# Memory_GPIO.net
KiCad netlist of a schematic drawn in Altium Designer
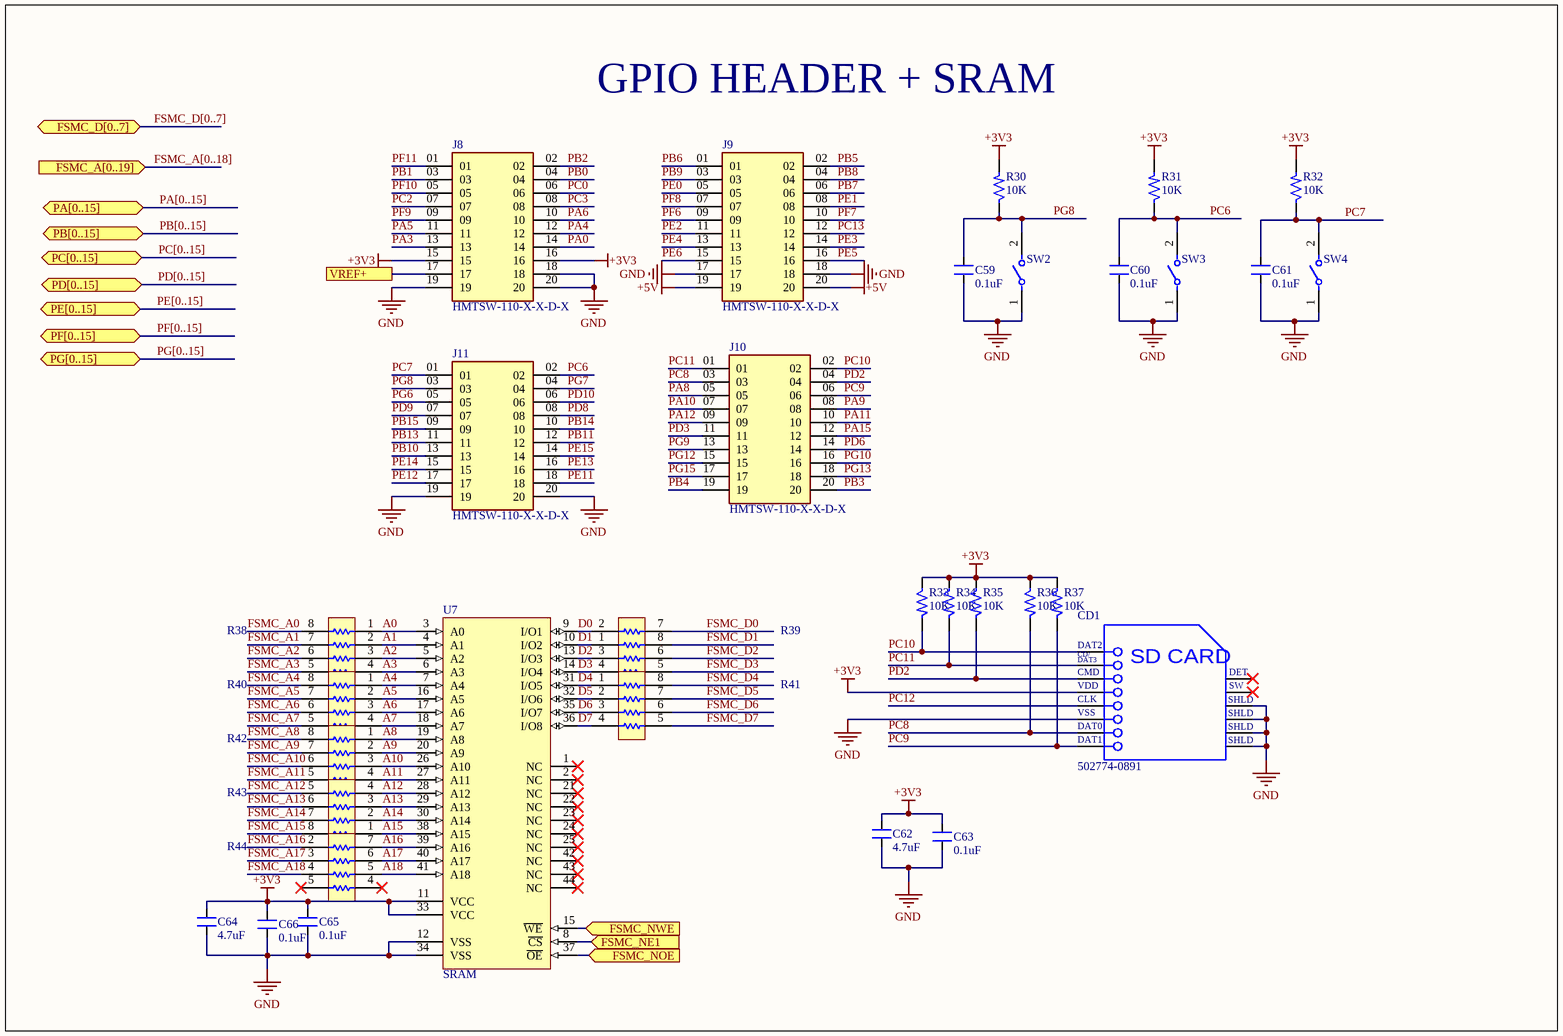
[diagram p0: Memory+GPIO.SchDoc]

(export (version "E")
  (design (tool "Eeschema 10.0.6"))
  (components
    (comp (ref "C59")
      (value "0.1uF")
      (footprint "CAP_0805")
      (description "0.1µF ±10% 50V Ceramic Capacitor X7R 0805 (2012 Metric)")
      (fields
        (field (name "MANUFACTURER") "Samsung")
        (field (name "MANUFACTURER PART NUMBER") "CL21B104KBCNNNC")
      )
      (libsource (lib "ESTEEMPCBLIB") (part "CAP_0.1uF-50V-10%-0805"))
    )
    (comp (ref "C60")
      (value "0.1uF")
      (footprint "CAP_0805")
      (description "0.1µF ±10% 50V Ceramic Capacitor X7R 0805 (2012 Metric)")
      (fields
        (field (name "MANUFACTURER") "Samsung")
        (field (name "MANUFACTURER PART NUMBER") "CL21B104KBCNNNC")
      )
      (libsource (lib "ESTEEMPCBLIB") (part "CAP_0.1uF-50V-10%-0805"))
    )
    (comp (ref "C61")
      (value "0.1uF")
      (footprint "CAP_0805")
      (description "0.1µF ±10% 50V Ceramic Capacitor X7R 0805 (2012 Metric)")
      (fields
        (field (name "MANUFACTURER") "Samsung")
        (field (name "MANUFACTURER PART NUMBER") "CL21B104KBCNNNC")
      )
      (libsource (lib "ESTEEMPCBLIB") (part "CAP_0.1uF-50V-10%-0805"))
    )
    (comp (ref "C62")
      (value "4.7uF")
      (footprint "CAP_0805")
      (description "4.7µF ±10% 50V Ceramic Capacitor X5R 0805 (2012 Metric)")
      (fields
        (field (name "MANUFACTURER") "Yageo")
        (field (name "MANUFACTURER PART NUMBER") "GRM21BR61H475KE51L")
      )
      (libsource (lib "ESTEEMPCBLIB") (part "CAP_4.7uF-50V-10%-0805"))
    )
    (comp (ref "C63")
      (value "0.1uF")
      (footprint "CAP_0805")
      (description "0.1µF ±10% 50V Ceramic Capacitor X7R 0805 (2012 Metric)")
      (fields
        (field (name "MANUFACTURER") "Samsung")
        (field (name "MANUFACTURER PART NUMBER") "CL21B104KBCNNNC")
      )
      (libsource (lib "ESTEEMPCBLIB") (part "CAP_0.1uF-50V-10%-0805"))
    )
    (comp (ref "C64")
      (value "4.7uF")
      (footprint "CAP_0805")
      (description "4.7µF ±10% 50V Ceramic Capacitor X5R 0805 (2012 Metric)")
      (fields
        (field (name "MANUFACTURER") "Yageo")
        (field (name "MANUFACTURER PART NUMBER") "GRM21BR61H475KE51L")
      )
      (libsource (lib "ESTEEMPCBLIB") (part "CAP_4.7uF-50V-10%-0805"))
    )
    (comp (ref "C65")
      (value "0.1uF")
      (footprint "CAP_0805")
      (description "0.1µF ±10% 50V Ceramic Capacitor X7R 0805 (2012 Metric)")
      (fields
        (field (name "MANUFACTURER") "Samsung")
        (field (name "MANUFACTURER PART NUMBER") "CL21B104KBCNNNC")
      )
      (libsource (lib "ESTEEMPCBLIB") (part "CAP_0.1uF-50V-10%-0805"))
    )
    (comp (ref "C66")
      (value "0.1uF")
      (footprint "CAP_0805")
      (description "0.1µF ±10% 50V Ceramic Capacitor X7R 0805 (2012 Metric)")
      (fields
        (field (name "MANUFACTURER") "Samsung")
        (field (name "MANUFACTURER PART NUMBER") "CL21B104KBCNNNC")
      )
      (libsource (lib "ESTEEMPCBLIB") (part "CAP_0.1uF-50V-10%-0805"))
    )
    (comp (ref "CD1")
      (value "502774-0891")
      (footprint "MOLX-502774-0891_V")
      (description "Micro SD Memory Card Connector, 0.5 A, 10 V (DC), -25 to 85 degC, 8-Pin SMT, RoHS, Tape and Reel")
      (fields (field (name "MANUFACTURER") "Molex"))
      (libsource (lib "Altium Content Vault") (part "CN-SD-8-2SW-4S_B"))
    )
    (comp (ref "J8")
      (value "HMTSW-110-X-X-D-X")
      (footprint "SAMTEC_HMTSW-110-X-X-D-X")
      (fields (field (name "MF") "Samtec") (field (name "MP") "HMTSW11008LMD330"))
      (libsource (lib "ESTEEMPCBLIB") (part "HMTSW-110-X-X-D-X"))
    )
    (comp (ref "J9")
      (value "HMTSW-110-X-X-D-X")
      (footprint "SAMTEC_HMTSW-110-X-X-D-X")
      (fields (field (name "MF") "Samtec") (field (name "MP") "HMTSW11008LMD330"))
      (libsource (lib "ESTEEMPCBLIB") (part "HMTSW-110-X-X-D-X"))
    )
    (comp (ref "J10")
      (value "HMTSW-110-X-X-D-X")
      (footprint "SAMTEC_HMTSW-110-X-X-D-X")
      (fields (field (name "MF") "Samtec") (field (name "MP") "HMTSW11008LMD330"))
      (libsource (lib "ESTEEMPCBLIB") (part "HMTSW-110-X-X-D-X"))
    )
    (comp (ref "J11")
      (value "HMTSW-110-X-X-D-X")
      (footprint "SAMTEC_HMTSW-110-X-X-D-X")
      (fields (field (name "MF") "Samtec") (field (name "MP") "HMTSW11008LMD330"))
      (libsource (lib "ESTEEMPCBLIB") (part "HMTSW-110-X-X-D-X"))
    )
    (comp (ref "R30")
      (value "10K")
      (footprint "RES_0603")
      (description "10 kOhms ±1% 0.1W, 1/10W Chip Resistor 0603 (1608 Metric) Automotive AEC-Q200 Thick Film")
      (fields (field (name "MANUFACTURER") "Walsin") (field (name "MANUFACTURER PART NUMBER") "WR06X1002FTL"))
      (libsource (lib "ESTEEMPCBLIB") (part "RES_10K-0.1W-1%-0603"))
    )
    (comp (ref "R31")
      (value "10K")
      (footprint "RES_0603")
      (description "10 kOhms ±1% 0.1W, 1/10W Chip Resistor 0603 (1608 Metric) Automotive AEC-Q200 Thick Film")
      (fields (field (name "MANUFACTURER") "Walsin") (field (name "MANUFACTURER PART NUMBER") "WR06X1002FTL"))
      (libsource (lib "ESTEEMPCBLIB") (part "RES_10K-0.1W-1%-0603"))
    )
    (comp (ref "R32")
      (value "10K")
      (footprint "RES_0603")
      (description "10 kOhms ±1% 0.1W, 1/10W Chip Resistor 0603 (1608 Metric) Automotive AEC-Q200 Thick Film")
      (fields (field (name "MANUFACTURER") "Walsin") (field (name "MANUFACTURER PART NUMBER") "WR06X1002FTL"))
      (libsource (lib "ESTEEMPCBLIB") (part "RES_10K-0.1W-1%-0603"))
    )
    (comp (ref "R33")
      (value "10K")
      (footprint "RES_0805")
      (description "10 kOhms ±1% 0.125W, 1/8W Chip Resistor 0805 (2012 Metric) Automotive AEC-Q200 Thick Film")
      (fields (field (name "MANUFACTURER") "CTS") (field (name "MANUFACTURER PART NUMBER") "WR08X1002FTL"))
      (libsource (lib "ESTEEMPCBLIB") (part "RES_10K-0.125W-1%-0805"))
    )
    (comp (ref "R34")
      (value "10K")
      (footprint "RES_0805")
      (description "10 kOhms ±1% 0.125W, 1/8W Chip Resistor 0805 (2012 Metric) Automotive AEC-Q200 Thick Film")
      (fields (field (name "MANUFACTURER") "CTS") (field (name "MANUFACTURER PART NUMBER") "WR08X1002FTL"))
      (libsource (lib "ESTEEMPCBLIB") (part "RES_10K-0.125W-1%-0805"))
    )
    (comp (ref "R35")
      (value "10K")
      (footprint "RES_0805")
      (description "10 kOhms ±1% 0.125W, 1/8W Chip Resistor 0805 (2012 Metric) Automotive AEC-Q200 Thick Film")
      (fields (field (name "MANUFACTURER") "CTS") (field (name "MANUFACTURER PART NUMBER") "WR08X1002FTL"))
      (libsource (lib "ESTEEMPCBLIB") (part "RES_10K-0.125W-1%-0805"))
    )
    (comp (ref "R36")
      (value "10K")
      (footprint "RES_0805")
      (description "10 kOhms ±1% 0.125W, 1/8W Chip Resistor 0805 (2012 Metric) Automotive AEC-Q200 Thick Film")
      (fields (field (name "MANUFACTURER") "CTS") (field (name "MANUFACTURER PART NUMBER") "WR08X1002FTL"))
      (libsource (lib "ESTEEMPCBLIB") (part "RES_10K-0.125W-1%-0805"))
    )
    (comp (ref "R37")
      (value "10K")
      (footprint "RES_0805")
      (description "10 kOhms ±1% 0.125W, 1/8W Chip Resistor 0805 (2012 Metric) Automotive AEC-Q200 Thick Film")
      (fields (field (name "MANUFACTURER") "CTS") (field (name "MANUFACTURER PART NUMBER") "WR08X1002FTL"))
      (libsource (lib "ESTEEMPCBLIB") (part "RES_10K-0.125W-1%-0805"))
    )
    (comp (ref "R38")
      (value "CAT16-103J4LF")
      (footprint "BOUR-CAT16-103J4LF_L")
      (fields (field (name "MANUFACTURER") "Bourns") (field (name "TOLERANCE") "±5%"))
      (libsource (lib "Altium Content Vault") (part "RES-P-8"))
    )
    (comp (ref "R39")
      (value "CAT16-103J4LF")
      (footprint "BOUR-CAT16-103J4LF_L")
      (fields (field (name "MANUFACTURER") "Bourns") (field (name "TOLERANCE") "±5%"))
      (libsource (lib "") (part "RES-P-8_3"))
    )
    (comp (ref "R40")
      (value "CAT16-103J4LF")
      (footprint "BOUR-CAT16-103J4LF_L")
      (fields (field (name "MANUFACTURER") "Bourns") (field (name "TOLERANCE") "±5%"))
      (libsource (lib "Altium Content Vault") (part "RES-P-8"))
    )
    (comp (ref "R41")
      (value "CAT16-103J4LF")
      (footprint "BOUR-CAT16-103J4LF_L")
      (fields (field (name "MANUFACTURER") "Bourns") (field (name "TOLERANCE") "±5%"))
      (libsource (lib "") (part "RES-P-8_2"))
    )
    (comp (ref "R42")
      (value "CAT16-103J4LF")
      (footprint "BOUR-CAT16-103J4LF_L")
      (fields (field (name "MANUFACTURER") "Bourns") (field (name "TOLERANCE") "±5%"))
      (libsource (lib "Altium Content Vault") (part "RES-P-8"))
    )
    (comp (ref "R43")
      (value "CAT16-103J4LF")
      (footprint "BOUR-CAT16-103J4LF_L")
      (fields (field (name "MANUFACTURER") "Bourns") (field (name "TOLERANCE") "±5%"))
      (libsource (lib "") (part "RES-P-8_1"))
    )
    (comp (ref "R44")
      (value "CAT16-103J4LF")
      (footprint "BOUR-CAT16-103J4LF_L")
      (fields (field (name "MANUFACTURER") "Bourns") (field (name "TOLERANCE") "±5%"))
      (libsource (lib "") (part "RES-P-8_4"))
    )
    (comp (ref "SW2")
      (value "147873-1")
      (footprint "FP-147873-1-MFG")
      (description "SWITCH TACTILE SPST-NO 0.05A 24V")
      (fields
        (field (name "MANUFACTURER") "TE Connectivity")
        (field (name "OCTOPART") "https://octopart.com/147873-1-te+connectivity-40818451")
      )
      (libsource (lib "Altium Content Vault") (part "bb27bde45df87f1f469753f287ef5ae"))
    )
    (comp (ref "SW3")
      (value "147873-1")
      (footprint "FP-147873-1-MFG")
      (description "SWITCH TACTILE SPST-NO 0.05A 24V")
      (fields
        (field (name "MANUFACTURER") "TE Connectivity")
        (field (name "OCTOPART") "https://octopart.com/147873-1-te+connectivity-40818451")
      )
      (libsource (lib "Altium Content Vault") (part "bb27bde45df87f1f469753f287ef5ae"))
    )
    (comp (ref "SW4")
      (value "147873-1")
      (footprint "FP-147873-1-MFG")
      (description "SWITCH TACTILE SPST-NO 0.05A 24V")
      (fields
        (field (name "MANUFACTURER") "TE Connectivity")
        (field (name "OCTOPART") "https://octopart.com/147873-1-te+connectivity-40818451")
      )
      (libsource (lib "Altium Content Vault") (part "bb27bde45df87f1f469753f287ef5ae"))
    )
    (comp (ref "U7")
      (value "SRAM")
      (footprint "CYP-TSOP-44_L")
      (description "4-Mbit (256 K x 16) Static RAM, 3 to 3.6 V, -40 to 85 degC, 44-Pin TSOP, RoHS, Tray")
      (fields (field (name "MANUFACTURER") "Cypress"))
      (libsource (lib "Persional LIB") (part "CMP-2000-06133-1"))
    )
  )
  (nets
    (net (code "44") (name "+3V3") (class "Default")
      (node (ref "C62") (pin "2") (pinfunction "2_2") (pintype "passive"))
      (node (ref "C63") (pin "2") (pinfunction "2_2") (pintype "passive"))
      (node (ref "C64") (pin "2") (pinfunction "2_2") (pintype "passive"))
      (node (ref "C65") (pin "2") (pinfunction "2_2") (pintype "passive"))
      (node (ref "C66") (pin "2") (pinfunction "2_2") (pintype "passive"))
      (node (ref "CD1") (pin "4") (pinfunction "VDD_4") (pintype "passive"))
      (node (ref "J8") (pin "15") (pinfunction "15_15") (pintype "passive"))
      (node (ref "J8") (pin "16") (pinfunction "16_16") (pintype "passive"))
      (node (ref "R30") (pin "2") (pinfunction "2_2") (pintype "passive"))
      (node (ref "R31") (pin "2") (pinfunction "2_2") (pintype "passive"))
      (node (ref "R32") (pin "2") (pinfunction "2_2") (pintype "passive"))
      (node (ref "R33") (pin "1") (pinfunction "1_1") (pintype "passive"))
      (node (ref "R34") (pin "1") (pinfunction "1_1") (pintype "passive"))
      (node (ref "R35") (pin "1") (pinfunction "1_1") (pintype "passive"))
      (node (ref "R36") (pin "1") (pinfunction "1_1") (pintype "passive"))
      (node (ref "R37") (pin "1") (pinfunction "1_1") (pintype "passive"))
      (node (ref "U7") (pin "11") (pinfunction "VCC_11") (pintype "power_in"))
      (node (ref "U7") (pin "33") (pinfunction "VCC_33") (pintype "power_in"))
    )
    (net (code "45") (name "+5V") (class "Default")
      (node (ref "J9") (pin "19") (pinfunction "19_19") (pintype "passive"))
      (node (ref "J9") (pin "20") (pinfunction "20_20") (pintype "passive"))
    )
    (net (code "46") (name "/A0") (class "Default")
      (node (ref "R38") (pin "1") (pinfunction "4_1") (pintype "passive"))
      (node (ref "U7") (pin "3") (pinfunction "A0_3") (pintype "input"))
    )
    (net (code "47") (name "/A1") (class "Default")
      (node (ref "R38") (pin "2") (pinfunction "3_2") (pintype "passive"))
      (node (ref "U7") (pin "4") (pinfunction "A1_4") (pintype "input"))
    )
    (net (code "48") (name "/A2") (class "Default")
      (node (ref "R38") (pin "3") (pinfunction "2_3") (pintype "passive"))
      (node (ref "U7") (pin "5") (pinfunction "A2_5") (pintype "input"))
    )
    (net (code "49") (name "/A3") (class "Default")
      (node (ref "R38") (pin "4") (pinfunction "1_4") (pintype "passive"))
      (node (ref "U7") (pin "6") (pinfunction "A3_6") (pintype "input"))
    )
    (net (code "50") (name "/A4") (class "Default")
      (node (ref "R40") (pin "1") (pinfunction "4_1") (pintype "passive"))
      (node (ref "U7") (pin "7") (pinfunction "A4_7") (pintype "input"))
    )
    (net (code "51") (name "/A5") (class "Default")
      (node (ref "R40") (pin "2") (pinfunction "3_2") (pintype "passive"))
      (node (ref "U7") (pin "16") (pinfunction "A5_16") (pintype "input"))
    )
    (net (code "52") (name "/A6") (class "Default")
      (node (ref "R40") (pin "3") (pinfunction "2_3") (pintype "passive"))
      (node (ref "U7") (pin "17") (pinfunction "A6_17") (pintype "input"))
    )
    (net (code "53") (name "/A7") (class "Default")
      (node (ref "R40") (pin "4") (pinfunction "1_4") (pintype "passive"))
      (node (ref "U7") (pin "18") (pinfunction "A7_18") (pintype "input"))
    )
    (net (code "54") (name "/A8") (class "Default")
      (node (ref "R42") (pin "1") (pinfunction "4_1") (pintype "passive"))
      (node (ref "U7") (pin "19") (pinfunction "A8_19") (pintype "input"))
    )
    (net (code "55") (name "/A9") (class "Default")
      (node (ref "R42") (pin "2") (pinfunction "3_2") (pintype "passive"))
      (node (ref "U7") (pin "20") (pinfunction "A9_20") (pintype "input"))
    )
    (net (code "56") (name "/A10") (class "Default")
      (node (ref "R42") (pin "3") (pinfunction "2_3") (pintype "passive"))
      (node (ref "U7") (pin "26") (pinfunction "A10_26") (pintype "input"))
    )
    (net (code "57") (name "/A11") (class "Default")
      (node (ref "R42") (pin "4") (pinfunction "1_4") (pintype "passive"))
      (node (ref "U7") (pin "27") (pinfunction "A11_27") (pintype "input"))
    )
    (net (code "58") (name "/A12") (class "Default")
      (node (ref "R43") (pin "4") (pinfunction "4_4") (pintype "passive"))
      (node (ref "U7") (pin "28") (pinfunction "A12_28") (pintype "input"))
    )
    (net (code "59") (name "/A13") (class "Default")
      (node (ref "R43") (pin "3") (pinfunction "3_3") (pintype "passive"))
      (node (ref "U7") (pin "29") (pinfunction "A13_29") (pintype "input"))
    )
    (net (code "60") (name "/A14") (class "Default")
      (node (ref "R43") (pin "2") (pinfunction "2_2") (pintype "passive"))
      (node (ref "U7") (pin "30") (pinfunction "A14_30") (pintype "input"))
    )
    (net (code "61") (name "/A15") (class "Default")
      (node (ref "R43") (pin "1") (pinfunction "1_1") (pintype "passive"))
      (node (ref "U7") (pin "38") (pinfunction "A15_38") (pintype "input"))
    )
    (net (code "62") (name "/A16") (class "Default")
      (node (ref "R44") (pin "7") (pinfunction "4_7") (pintype "passive"))
      (node (ref "U7") (pin "39") (pinfunction "A16_39") (pintype "input"))
    )
    (net (code "63") (name "/A17") (class "Default")
      (node (ref "R44") (pin "6") (pinfunction "3_6") (pintype "passive"))
      (node (ref "U7") (pin "40") (pinfunction "A17_40") (pintype "input"))
    )
    (net (code "64") (name "/A18") (class "Default")
      (node (ref "R44") (pin "5") (pinfunction "2_5") (pintype "passive"))
      (node (ref "U7") (pin "41") (pinfunction "A18_41") (pintype "input"))
    )
    (net (code "65") (name "/D0") (class "Default")
      (node (ref "R39") (pin "2") (pinfunction "1_2") (pintype "passive"))
      (node (ref "U7") (pin "9") (pinfunction "I/O1_9") (pintype "bidirectional"))
    )
    (net (code "66") (name "/D1") (class "Default")
      (node (ref "R39") (pin "1") (pinfunction "2_1") (pintype "passive"))
      (node (ref "U7") (pin "10") (pinfunction "I/O2_10") (pintype "bidirectional"))
    )
    (net (code "67") (name "/D2") (class "Default")
      (node (ref "R39") (pin "3") (pinfunction "3_3") (pintype "passive"))
      (node (ref "U7") (pin "13") (pinfunction "I/O3_13") (pintype "bidirectional"))
    )
    (net (code "68") (name "/D3") (class "Default")
      (node (ref "R39") (pin "4") (pinfunction "4_4") (pintype "passive"))
      (node (ref "U7") (pin "14") (pinfunction "I/O4_14") (pintype "bidirectional"))
    )
    (net (code "69") (name "/D4") (class "Default")
      (node (ref "R41") (pin "1") (pinfunction "1_1") (pintype "passive"))
      (node (ref "U7") (pin "31") (pinfunction "I/O5_31") (pintype "bidirectional"))
    )
    (net (code "70") (name "/D5") (class "Default")
      (node (ref "R41") (pin "2") (pinfunction "2_2") (pintype "passive"))
      (node (ref "U7") (pin "32") (pinfunction "I/O6_32") (pintype "bidirectional"))
    )
    (net (code "71") (name "/D6") (class "Default")
      (node (ref "R41") (pin "3") (pinfunction "3_3") (pintype "passive"))
      (node (ref "U7") (pin "35") (pinfunction "I/O7_35") (pintype "bidirectional"))
    )
    (net (code "72") (name "/D7") (class "Default")
      (node (ref "R41") (pin "4") (pinfunction "4_4") (pintype "passive"))
      (node (ref "U7") (pin "36") (pinfunction "I/O8_36") (pintype "bidirectional"))
    )
    (net (code "73") (name "/FSMC_A0") (class "Default")
      (node (ref "R38") (pin "8") (pinfunction "5_8") (pintype "passive"))
    )
    (net (code "74") (name "/FSMC_A1") (class "Default")
      (node (ref "R38") (pin "7") (pinfunction "6_7") (pintype "passive"))
    )
    (net (code "75") (name "/FSMC_A2") (class "Default")
      (node (ref "R38") (pin "6") (pinfunction "7_6") (pintype "passive"))
    )
    (net (code "76") (name "/FSMC_A3") (class "Default")
      (node (ref "R38") (pin "5") (pinfunction "8_5") (pintype "passive"))
    )
    (net (code "77") (name "/FSMC_A4") (class "Default")
      (node (ref "R40") (pin "8") (pinfunction "5_8") (pintype "passive"))
    )
    (net (code "78") (name "/FSMC_A5") (class "Default")
      (node (ref "R40") (pin "7") (pinfunction "6_7") (pintype "passive"))
    )
    (net (code "79") (name "/FSMC_A6") (class "Default")
      (node (ref "R40") (pin "6") (pinfunction "7_6") (pintype "passive"))
    )
    (net (code "80") (name "/FSMC_A7") (class "Default")
      (node (ref "R40") (pin "5") (pinfunction "8_5") (pintype "passive"))
    )
    (net (code "81") (name "/FSMC_A8") (class "Default")
      (node (ref "R42") (pin "8") (pinfunction "5_8") (pintype "passive"))
    )
    (net (code "82") (name "/FSMC_A9") (class "Default")
      (node (ref "R42") (pin "7") (pinfunction "6_7") (pintype "passive"))
    )
    (net (code "83") (name "/FSMC_A10") (class "Default")
      (node (ref "R42") (pin "6") (pinfunction "7_6") (pintype "passive"))
    )
    (net (code "84") (name "/FSMC_A11") (class "Default")
      (node (ref "R42") (pin "5") (pinfunction "8_5") (pintype "passive"))
    )
    (net (code "85") (name "/FSMC_A12") (class "Default")
      (node (ref "R43") (pin "5") (pinfunction "5_5") (pintype "passive"))
    )
    (net (code "86") (name "/FSMC_A13") (class "Default")
      (node (ref "R43") (pin "6") (pinfunction "6_6") (pintype "passive"))
    )
    (net (code "87") (name "/FSMC_A14") (class "Default")
      (node (ref "R43") (pin "7") (pinfunction "7_7") (pintype "passive"))
    )
    (net (code "88") (name "/FSMC_A15") (class "Default")
      (node (ref "R43") (pin "8") (pinfunction "8_8") (pintype "passive"))
    )
    (net (code "89") (name "/FSMC_A16") (class "Default")
      (node (ref "R44") (pin "2") (pinfunction "5_2") (pintype "passive"))
    )
    (net (code "90") (name "/FSMC_A17") (class "Default")
      (node (ref "R44") (pin "3") (pinfunction "6_3") (pintype "passive"))
    )
    (net (code "91") (name "/FSMC_A18") (class "Default")
      (node (ref "R44") (pin "4") (pinfunction "7_4") (pintype "passive"))
    )
    (net (code "93") (name "/FSMC_D0") (class "Default")
      (node (ref "R39") (pin "7") (pinfunction "8_7") (pintype "passive"))
    )
    (net (code "94") (name "/FSMC_D1") (class "Default")
      (node (ref "R39") (pin "8") (pinfunction "7_8") (pintype "passive"))
    )
    (net (code "95") (name "/FSMC_D2") (class "Default")
      (node (ref "R39") (pin "6") (pinfunction "6_6") (pintype "passive"))
    )
    (net (code "96") (name "/FSMC_D3") (class "Default")
      (node (ref "R39") (pin "5") (pinfunction "5_5") (pintype "passive"))
    )
    (net (code "97") (name "/FSMC_D4") (class "Default")
      (node (ref "R41") (pin "8") (pinfunction "8_8") (pintype "passive"))
    )
    (net (code "98") (name "/FSMC_D5") (class "Default")
      (node (ref "R41") (pin "7") (pinfunction "7_7") (pintype "passive"))
    )
    (net (code "99") (name "/FSMC_D6") (class "Default")
      (node (ref "R41") (pin "6") (pinfunction "6_6") (pintype "passive"))
    )
    (net (code "100") (name "/FSMC_D7") (class "Default")
      (node (ref "R41") (pin "5") (pinfunction "5_5") (pintype "passive"))
    )
    (net (code "102") (name "/FSMC_NE1") (class "Default")
      (node (ref "U7") (pin "8") (pinfunction "~{CS}_8") (pintype "input"))
    )
    (net (code "103") (name "/FSMC_NOE") (class "Default")
      (node (ref "U7") (pin "37") (pinfunction "~{OE}_37") (pintype "input"))
    )
    (net (code "104") (name "/FSMC_NWE") (class "Default")
      (node (ref "U7") (pin "15") (pinfunction "~{WE}_15") (pintype "input"))
    )
    (net (code "105") (name "/PA0") (class "Default")
      (node (ref "J8") (pin "14") (pinfunction "14_14") (pintype "passive"))
    )
    (net (code "106") (name "/PA3") (class "Default")
      (node (ref "J8") (pin "13") (pinfunction "13_13") (pintype "passive"))
    )
    (net (code "107") (name "/PA4") (class "Default")
      (node (ref "J8") (pin "12") (pinfunction "12_12") (pintype "passive"))
    )
    (net (code "108") (name "/PA5") (class "Default")
      (node (ref "J8") (pin "11") (pinfunction "11_11") (pintype "passive"))
    )
    (net (code "109") (name "/PA6") (class "Default")
      (node (ref "J8") (pin "10") (pinfunction "10_10") (pintype "passive"))
    )
    (net (code "110") (name "/PA8") (class "Default")
      (node (ref "J10") (pin "05") (pinfunction "05_05") (pintype "passive"))
    )
    (net (code "111") (name "/PA9") (class "Default")
      (node (ref "J10") (pin "08") (pinfunction "08_08") (pintype "passive"))
    )
    (net (code "112") (name "/PA10") (class "Default")
      (node (ref "J10") (pin "07") (pinfunction "07_07") (pintype "passive"))
    )
    (net (code "113") (name "/PA11") (class "Default")
      (node (ref "J10") (pin "10") (pinfunction "10_10") (pintype "passive"))
    )
    (net (code "114") (name "/PA12") (class "Default")
      (node (ref "J10") (pin "09") (pinfunction "09_09") (pintype "passive"))
    )
    (net (code "115") (name "/PA15") (class "Default")
      (node (ref "J10") (pin "12") (pinfunction "12_12") (pintype "passive"))
    )
    (net (code "117") (name "/PB0") (class "Default")
      (node (ref "J8") (pin "04") (pinfunction "04_04") (pintype "passive"))
    )
    (net (code "118") (name "/PB1") (class "Default")
      (node (ref "J8") (pin "03") (pinfunction "03_03") (pintype "passive"))
    )
    (net (code "119") (name "/PB2") (class "Default")
      (node (ref "J8") (pin "02") (pinfunction "02_02") (pintype "passive"))
    )
    (net (code "120") (name "/PB3") (class "Default")
      (node (ref "J10") (pin "20") (pinfunction "20_20") (pintype "passive"))
    )
    (net (code "121") (name "/PB4") (class "Default")
      (node (ref "J10") (pin "19") (pinfunction "19_19") (pintype "passive"))
    )
    (net (code "122") (name "/PB5") (class "Default")
      (node (ref "J9") (pin "02") (pinfunction "02_02") (pintype "passive"))
    )
    (net (code "123") (name "/PB6") (class "Default")
      (node (ref "J9") (pin "01") (pinfunction "01_01") (pintype "passive"))
    )
    (net (code "124") (name "/PB7") (class "Default")
      (node (ref "J9") (pin "06") (pinfunction "06_06") (pintype "passive"))
    )
    (net (code "125") (name "/PB8") (class "Default")
      (node (ref "J9") (pin "04") (pinfunction "04_04") (pintype "passive"))
    )
    (net (code "126") (name "/PB9") (class "Default")
      (node (ref "J9") (pin "03") (pinfunction "03_03") (pintype "passive"))
    )
    (net (code "127") (name "/PB10") (class "Default")
      (node (ref "J11") (pin "13") (pinfunction "13_13") (pintype "passive"))
    )
    (net (code "128") (name "/PB11") (class "Default")
      (node (ref "J11") (pin "12") (pinfunction "12_12") (pintype "passive"))
    )
    (net (code "129") (name "/PB13") (class "Default")
      (node (ref "J11") (pin "11") (pinfunction "11_11") (pintype "passive"))
    )
    (net (code "130") (name "/PB14") (class "Default")
      (node (ref "J11") (pin "10") (pinfunction "10_10") (pintype "passive"))
    )
    (net (code "131") (name "/PB15") (class "Default")
      (node (ref "J11") (pin "09") (pinfunction "09_09") (pintype "passive"))
    )
    (net (code "133") (name "/PC0") (class "Default")
      (node (ref "J8") (pin "06") (pinfunction "06_06") (pintype "passive"))
    )
    (net (code "134") (name "/PC2") (class "Default")
      (node (ref "J8") (pin "07") (pinfunction "07_07") (pintype "passive"))
    )
    (net (code "135") (name "/PC3") (class "Default")
      (node (ref "J8") (pin "08") (pinfunction "08_08") (pintype "passive"))
    )
    (net (code "136") (name "/PC6") (class "Default")
      (node (ref "C60") (pin "2") (pinfunction "2_2") (pintype "passive"))
      (node (ref "J11") (pin "02") (pinfunction "02_02") (pintype "passive"))
      (node (ref "R31") (pin "1") (pinfunction "1_1") (pintype "passive"))
      (node (ref "SW3") (pin "2") (pinfunction "2_2") (pintype "passive"))
    )
    (net (code "137") (name "/PC7") (class "Default")
      (node (ref "C61") (pin "2") (pinfunction "2_2") (pintype "passive"))
      (node (ref "J11") (pin "01") (pinfunction "01_01") (pintype "passive"))
      (node (ref "R32") (pin "1") (pinfunction "1_1") (pintype "passive"))
      (node (ref "SW4") (pin "2") (pinfunction "2_2") (pintype "passive"))
    )
    (net (code "138") (name "/PC8") (class "Default")
      (node (ref "CD1") (pin "7") (pinfunction "DAT0_7") (pintype "passive"))
      (node (ref "J10") (pin "03") (pinfunction "03_03") (pintype "passive"))
      (node (ref "R36") (pin "2") (pinfunction "2_2") (pintype "passive"))
    )
    (net (code "139") (name "/PC9") (class "Default")
      (node (ref "CD1") (pin "8") (pinfunction "DAT1_8") (pintype "passive"))
      (node (ref "J10") (pin "06") (pinfunction "06_06") (pintype "passive"))
      (node (ref "R37") (pin "2") (pinfunction "2_2") (pintype "passive"))
    )
    (net (code "140") (name "/PC10") (class "Default")
      (node (ref "CD1") (pin "1") (pinfunction "DAT2_1") (pintype "passive"))
      (node (ref "J10") (pin "02") (pinfunction "02_02") (pintype "passive"))
      (node (ref "R33") (pin "2") (pinfunction "2_2") (pintype "passive"))
    )
    (net (code "141") (name "/PC11") (class "Default")
      (node (ref "CD1") (pin "2") (pinfunction "CD/DAT3_2") (pintype "passive"))
      (node (ref "J10") (pin "01") (pinfunction "01_01") (pintype "passive"))
      (node (ref "R34") (pin "2") (pinfunction "2_2") (pintype "passive"))
    )
    (net (code "142") (name "/PC12") (class "Default")
      (node (ref "CD1") (pin "5") (pinfunction "CLK_5") (pintype "passive"))
    )
    (net (code "143") (name "/PC13") (class "Default")
      (node (ref "J9") (pin "12") (pinfunction "12_12") (pintype "passive"))
    )
    (net (code "145") (name "/PD2") (class "Default")
      (node (ref "CD1") (pin "3") (pinfunction "CMD_3") (pintype "passive"))
      (node (ref "J10") (pin "04") (pinfunction "04_04") (pintype "passive"))
      (node (ref "R35") (pin "2") (pinfunction "2_2") (pintype "passive"))
    )
    (net (code "146") (name "/PD3") (class "Default")
      (node (ref "J10") (pin "11") (pinfunction "11_11") (pintype "passive"))
    )
    (net (code "147") (name "/PD6") (class "Default")
      (node (ref "J10") (pin "14") (pinfunction "14_14") (pintype "passive"))
    )
    (net (code "148") (name "/PD8") (class "Default")
      (node (ref "J11") (pin "08") (pinfunction "08_08") (pintype "passive"))
    )
    (net (code "149") (name "/PD9") (class "Default")
      (node (ref "J11") (pin "07") (pinfunction "07_07") (pintype "passive"))
    )
    (net (code "150") (name "/PD10") (class "Default")
      (node (ref "J11") (pin "06") (pinfunction "06_06") (pintype "passive"))
    )
    (net (code "152") (name "/PE0") (class "Default")
      (node (ref "J9") (pin "05") (pinfunction "05_05") (pintype "passive"))
    )
    (net (code "153") (name "/PE1") (class "Default")
      (node (ref "J9") (pin "08") (pinfunction "08_08") (pintype "passive"))
    )
    (net (code "154") (name "/PE2") (class "Default")
      (node (ref "J9") (pin "11") (pinfunction "11_11") (pintype "passive"))
    )
    (net (code "155") (name "/PE3") (class "Default")
      (node (ref "J9") (pin "14") (pinfunction "14_14") (pintype "passive"))
    )
    (net (code "156") (name "/PE4") (class "Default")
      (node (ref "J9") (pin "13") (pinfunction "13_13") (pintype "passive"))
    )
    (net (code "157") (name "/PE5") (class "Default")
      (node (ref "J9") (pin "16") (pinfunction "16_16") (pintype "passive"))
    )
    (net (code "158") (name "/PE6") (class "Default")
      (node (ref "J9") (pin "15") (pinfunction "15_15") (pintype "passive"))
    )
    (net (code "159") (name "/PE11") (class "Default")
      (node (ref "J11") (pin "18") (pinfunction "18_18") (pintype "passive"))
    )
    (net (code "160") (name "/PE12") (class "Default")
      (node (ref "J11") (pin "17") (pinfunction "17_17") (pintype "passive"))
    )
    (net (code "161") (name "/PE13") (class "Default")
      (node (ref "J11") (pin "16") (pinfunction "16_16") (pintype "passive"))
    )
    (net (code "162") (name "/PE14") (class "Default")
      (node (ref "J11") (pin "15") (pinfunction "15_15") (pintype "passive"))
    )
    (net (code "163") (name "/PE15") (class "Default")
      (node (ref "J11") (pin "14") (pinfunction "14_14") (pintype "passive"))
    )
    (net (code "165") (name "/PF6") (class "Default")
      (node (ref "J9") (pin "09") (pinfunction "09_09") (pintype "passive"))
    )
    (net (code "166") (name "/PF7") (class "Default")
      (node (ref "J9") (pin "10") (pinfunction "10_10") (pintype "passive"))
    )
    (net (code "167") (name "/PF8") (class "Default")
      (node (ref "J9") (pin "07") (pinfunction "07_07") (pintype "passive"))
    )
    (net (code "168") (name "/PF9") (class "Default")
      (node (ref "J8") (pin "09") (pinfunction "09_09") (pintype "passive"))
    )
    (net (code "169") (name "/PF10") (class "Default")
      (node (ref "J8") (pin "05") (pinfunction "05_05") (pintype "passive"))
    )
    (net (code "170") (name "/PF11") (class "Default")
      (node (ref "J8") (pin "01") (pinfunction "01_01") (pintype "passive"))
    )
    (net (code "172") (name "/PG6") (class "Default")
      (node (ref "J11") (pin "05") (pinfunction "05_05") (pintype "passive"))
    )
    (net (code "173") (name "/PG7") (class "Default")
      (node (ref "J11") (pin "04") (pinfunction "04_04") (pintype "passive"))
    )
    (net (code "174") (name "/PG8") (class "Default")
      (node (ref "C59") (pin "2") (pinfunction "2_2") (pintype "passive"))
      (node (ref "J11") (pin "03") (pinfunction "03_03") (pintype "passive"))
      (node (ref "R30") (pin "1") (pinfunction "1_1") (pintype "passive"))
      (node (ref "SW2") (pin "2") (pinfunction "2_2") (pintype "passive"))
    )
    (net (code "175") (name "/PG9") (class "Default")
      (node (ref "J10") (pin "13") (pinfunction "13_13") (pintype "passive"))
    )
    (net (code "176") (name "/PG10") (class "Default")
      (node (ref "J10") (pin "16") (pinfunction "16_16") (pintype "passive"))
    )
    (net (code "177") (name "/PG12") (class "Default")
      (node (ref "J10") (pin "15") (pinfunction "15_15") (pintype "passive"))
    )
    (net (code "178") (name "/PG13") (class "Default")
      (node (ref "J10") (pin "18") (pinfunction "18_18") (pintype "passive"))
    )
    (net (code "179") (name "/PG15") (class "Default")
      (node (ref "J10") (pin "17") (pinfunction "17_17") (pintype "passive"))
    )
    (net (code "181") (name "/VREF+") (class "Default")
      (node (ref "J8") (pin "17") (pinfunction "17_17") (pintype "passive"))
    )
    (net (code "182") (name "GND") (class "Default")
      (node (ref "C59") (pin "1") (pinfunction "1_1") (pintype "passive"))
      (node (ref "C60") (pin "1") (pinfunction "1_1") (pintype "passive"))
      (node (ref "C61") (pin "1") (pinfunction "1_1") (pintype "passive"))
      (node (ref "C62") (pin "1") (pinfunction "1_1") (pintype "passive"))
      (node (ref "C63") (pin "1") (pinfunction "1_1") (pintype "passive"))
      (node (ref "C64") (pin "1") (pinfunction "1_1") (pintype "passive"))
      (node (ref "C65") (pin "1") (pinfunction "1_1") (pintype "passive"))
      (node (ref "C66") (pin "1") (pinfunction "1_1") (pintype "passive"))
      (node (ref "CD1") (pin "11") (pinfunction "SHLD_11") (pintype "passive"))
      (node (ref "CD1") (pin "12") (pinfunction "SHLD_12") (pintype "passive"))
      (node (ref "CD1") (pin "13") (pinfunction "SHLD_13") (pintype "passive"))
      (node (ref "CD1") (pin "14") (pinfunction "SHLD_14") (pintype "passive"))
      (node (ref "CD1") (pin "6") (pinfunction "VSS_6") (pintype "passive"))
      (node (ref "J11") (pin "19") (pinfunction "19_19") (pintype "passive"))
      (node (ref "J11") (pin "20") (pinfunction "20_20") (pintype "passive"))
      (node (ref "J8") (pin "18") (pinfunction "18_18") (pintype "passive"))
      (node (ref "J8") (pin "19") (pinfunction "19_19") (pintype "passive"))
      (node (ref "J8") (pin "20") (pinfunction "20_20") (pintype "passive"))
      (node (ref "J9") (pin "17") (pinfunction "17_17") (pintype "passive"))
      (node (ref "J9") (pin "18") (pinfunction "18_18") (pintype "passive"))
      (node (ref "SW2") (pin "1") (pinfunction "1_1") (pintype "passive"))
      (node (ref "SW3") (pin "1") (pinfunction "1_1") (pintype "passive"))
      (node (ref "SW4") (pin "1") (pinfunction "1_1") (pintype "passive"))
      (node (ref "U7") (pin "12") (pinfunction "VSS_12") (pintype "passive"))
      (node (ref "U7") (pin "34") (pinfunction "VSS_34") (pintype "passive"))
    )
    (net (code "183") (name "unconnected-(CD1-DETECT-Pad9)") (class "Default")
      (node (ref "CD1") (pin "9") (pinfunction "DETECT_9") (pintype "passive+no_connect"))
    )
    (net (code "184") (name "unconnected-(CD1-SWITCH-Pad10)") (class "Default")
      (node (ref "CD1") (pin "10") (pinfunction "SWITCH_10") (pintype "passive+no_connect"))
    )
    (net (code "185") (name "unconnected-(R44-1-Pad4)") (class "Default")
      (node (ref "R44") (pin "4") (pinfunction "1_4") (pintype "passive+no_connect"))
    )
    (net (code "186") (name "unconnected-(R44-8-Pad5)") (class "Default")
      (node (ref "R44") (pin "5") (pinfunction "8_5") (pintype "passive+no_connect"))
    )
    (net (code "187") (name "unconnected-(U7-NC-Pad1)") (class "Default")
      (node (ref "U7") (pin "1") (pinfunction "NC_1") (pintype "open_collector+no_connect"))
    )
    (net (code "188") (name "unconnected-(U7-NC-Pad2)") (class "Default")
      (node (ref "U7") (pin "2") (pinfunction "NC_2") (pintype "open_collector+no_connect"))
    )
    (net (code "189") (name "unconnected-(U7-NC-Pad21)") (class "Default")
      (node (ref "U7") (pin "21") (pinfunction "NC_21") (pintype "passive+no_connect"))
    )
    (net (code "190") (name "unconnected-(U7-NC-Pad22)") (class "Default")
      (node (ref "U7") (pin "22") (pinfunction "NC_22") (pintype "passive+no_connect"))
    )
    (net (code "191") (name "unconnected-(U7-NC-Pad23)") (class "Default")
      (node (ref "U7") (pin "23") (pinfunction "NC_23") (pintype "open_collector+no_connect"))
    )
    (net (code "192") (name "unconnected-(U7-NC-Pad24)") (class "Default")
      (node (ref "U7") (pin "24") (pinfunction "NC_24") (pintype "open_collector+no_connect"))
    )
    (net (code "193") (name "unconnected-(U7-NC-Pad25)") (class "Default")
      (node (ref "U7") (pin "25") (pinfunction "NC_25") (pintype "passive+no_connect"))
    )
    (net (code "194") (name "unconnected-(U7-NC-Pad42)") (class "Default")
      (node (ref "U7") (pin "42") (pinfunction "NC_42") (pintype "passive+no_connect"))
    )
    (net (code "195") (name "unconnected-(U7-NC-Pad43)") (class "Default")
      (node (ref "U7") (pin "43") (pinfunction "NC_43") (pintype "open_collector+no_connect"))
    )
    (net (code "196") (name "unconnected-(U7-NC-Pad44)") (class "Default")
      (node (ref "U7") (pin "44") (pinfunction "NC_44") (pintype "passive+no_connect"))
    )
  )
)
